# pca10156_sheet1_connections.net
KiCad netlist of a schematic drawn in Altium Designer
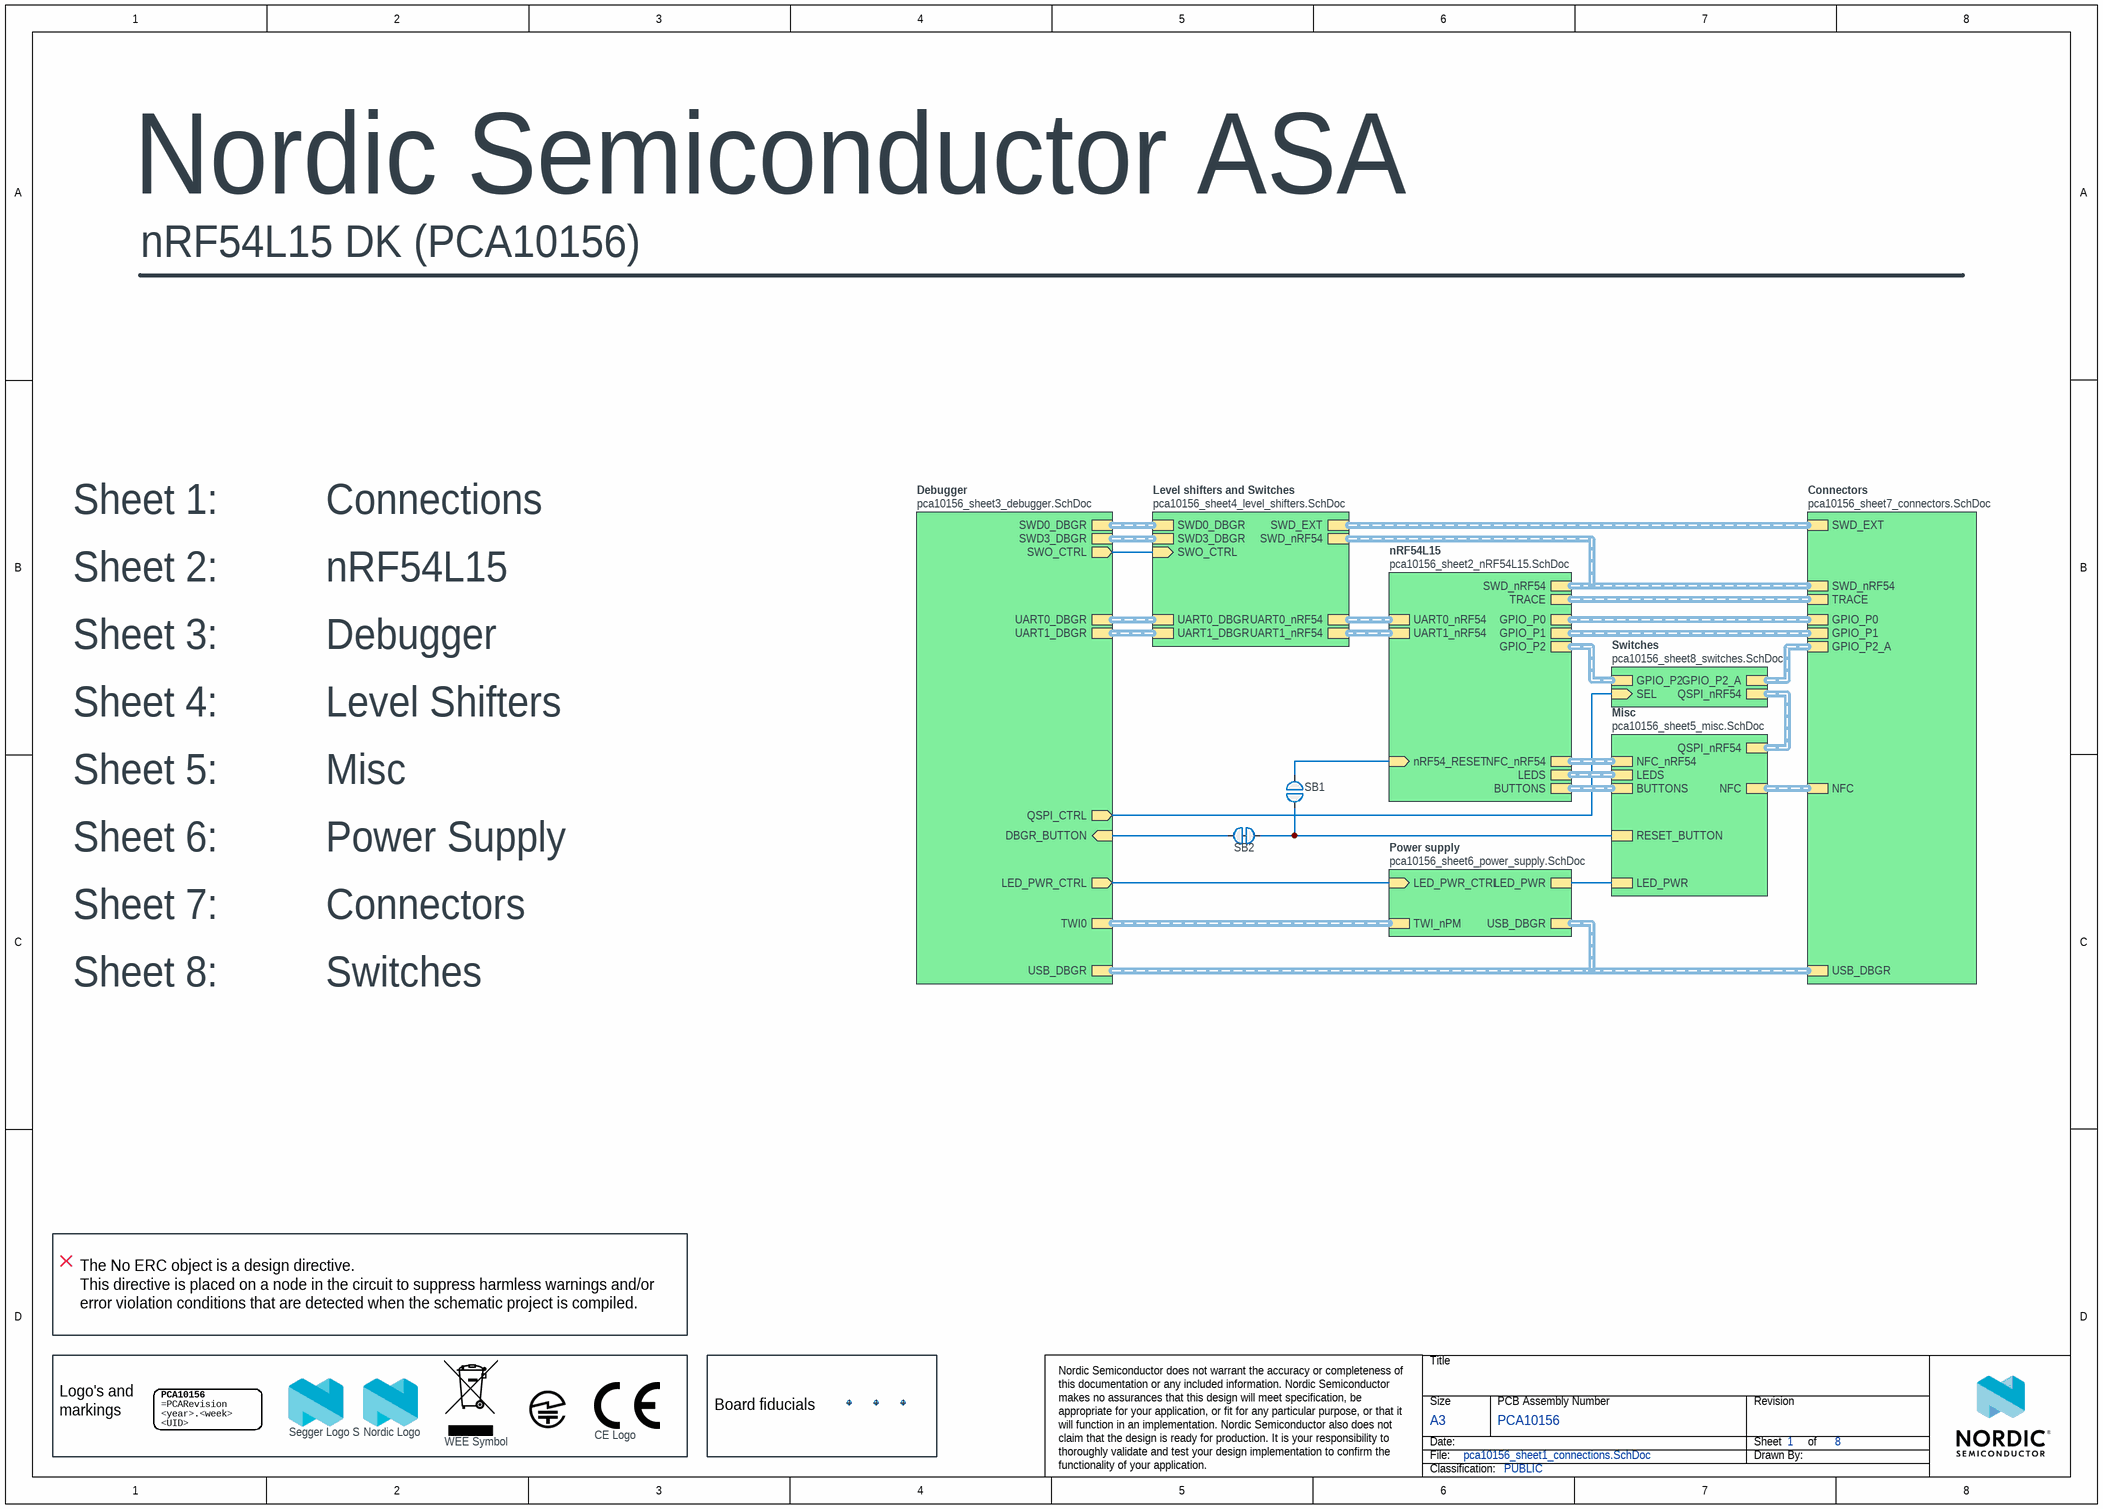
[diagram p0: pca10156_sheet1_connections.SchDoc]

(export (version "E")
  (design (tool "Eeschema 10.0.6"))
  (components
    (comp (ref "Fid1")
      (value "Fiducial mark")
      (footprint "Fiducial")
      (description "Fiducial Mark")
      (fields
        (field (name "PART NUMBER") "Fid-Mark")
        (field (name "MANUFACTURER") "N.A.")
        (field (name "AUTHOR") "rsk")
      )
      (libsource (lib "AltiumLib") (part "Fiducial"))
    )
    (comp (ref "Fid2")
      (value "Fiducial mark")
      (footprint "Fiducial")
      (description "Fiducial Mark")
      (fields
        (field (name "PART NUMBER") "Fid-Mark")
        (field (name "MANUFACTURER") "N.A.")
        (field (name "AUTHOR") "rsk")
      )
      (libsource (lib "AltiumLib") (part "Fiducial"))
    )
    (comp (ref "Fid3")
      (value "Fiducial mark")
      (footprint "Fiducial")
      (description "Fiducial Mark")
      (fields
        (field (name "PART NUMBER") "Fid-Mark")
        (field (name "MANUFACTURER") "N.A.")
        (field (name "AUTHOR") "rsk")
      )
      (libsource (lib "AltiumLib") (part "Fiducial"))
    )
    (comp (ref "LABEL1")
      (value "12x12mm")
      (footprint "LabelSilk_12x12")
      (description "PCA version label, stick-on, 12x12mm")
      (fields
        (field (name "PART NUMBER") "Label_12x12")
        (field (name "MANUFACTURER") "Ellco Etikett")
        (field (name "AUTHOR") "hany")
      )
      (libsource (lib "AltiumLib") (part "Label_Stick-on-4-lines"))
    )
    (comp (ref "LOGO1")
      (value "Nordic Logo")
      (footprint "NORDIC_LOGO_LYING")
      (description "Nordic logo lying")
      (fields
        (field (name "PART NUMBER") "Nordic Logo lying")
        (field (name "MANUFACTURER") "N.A.")
        (field (name "AUTHOR") "rsk")
      )
      (libsource (lib "AltiumLib") (part "Nordic Logo"))
    )
    (comp (ref "LOGO2")
      (value "WEE Symbol")
      (footprint "WEE_3x4.5mm")
      (description "WEEE Directive symbol")
      (fields
        (field (name "PART NUMBER") "WEEE Symbol 3x4.5mm")
        (field (name "MANUFACTURER") "N.A.")
        (field (name "AUTHOR") "rsk")
      )
      (libsource (lib "AltiumLib") (part "WEEE Directive Logo"))
    )
    (comp (ref "LOGO3")
      (value "Segger Logo S")
      (footprint "SEGGER_LOGO_S")
      (description "Segger logo, small size")
      (fields (field (name "MANUFACTURER") "N.A.") (field (name "AUTHOR") "rsk"))
      (libsource (lib "AltiumLib") (part "Nordic Logo"))
    )
    (comp (ref "LOGO4")
      (value "CE Logo")
      (footprint "CE_logo")
      (description "CE (Conformité_Européenne) logo")
      (fields
        (field (name "PART NUMBER") "CE_logo")
        (field (name "MANUFACTURER") "N.A.")
        (field (name "AUTHOR") "daba")
      )
      (libsource (lib "AltiumLib") (part "CE logo"))
    )
    (comp (ref "S1")
      (value "Giteki Symbol")
      (footprint "Giteki")
      (description "Giteki symbol")
      (fields (field (name "MANUFACTURER") "N.A.") (field (name "AUTHOR") "getr"))
      (libsource (lib "AltiumLib") (part "Giteki"))
    )
    (comp (ref "SB1")
      (value "Solderbridge")
      (footprint "Solderbridge")
      (fields (field (name "MANUFACTURER") "N.A.") (field (name "AUTHOR") "rsk"))
      (libsource (lib "AltiumLib") (part "SOLDERBRIDGE"))
    )
    (comp (ref "SB2")
      (value "Solderbridge")
      (footprint "Solderbridge_Shorted")
      (description "Shorted Solderbridge")
      (fields
        (field (name "PART NUMBER") "Solderbridge Shorted")
        (field (name "MANUFACTURER") "N.A.")
        (field (name "AUTHOR") "rsk")
      )
      (libsource (lib "AltiumLib") (part "SOLDERBRIDGE_SHORTED"))
    )
  )
  (nets
    (net (code "2") (name "/DBGR_BUTTON") (class "Default")
      (node (ref "SB2") (pin "2") (pinfunction "1_2") (pintype "passive"))
    )
    (net (code "14") (name "/RESET_BUTTON") (class "Default")
      (node (ref "SB1") (pin "2") (pinfunction "1_2") (pintype "passive"))
      (node (ref "SB2") (pin "1") (pinfunction "0_1") (pintype "passive"))
    )
    (net (code "27") (name "/nRF54_RESET") (class "Default")
      (node (ref "SB1") (pin "1") (pinfunction "0_1") (pintype "passive"))
    )
  )
)
